# Fermento.net
KiCad netlist of a schematic drawn in EAGLE
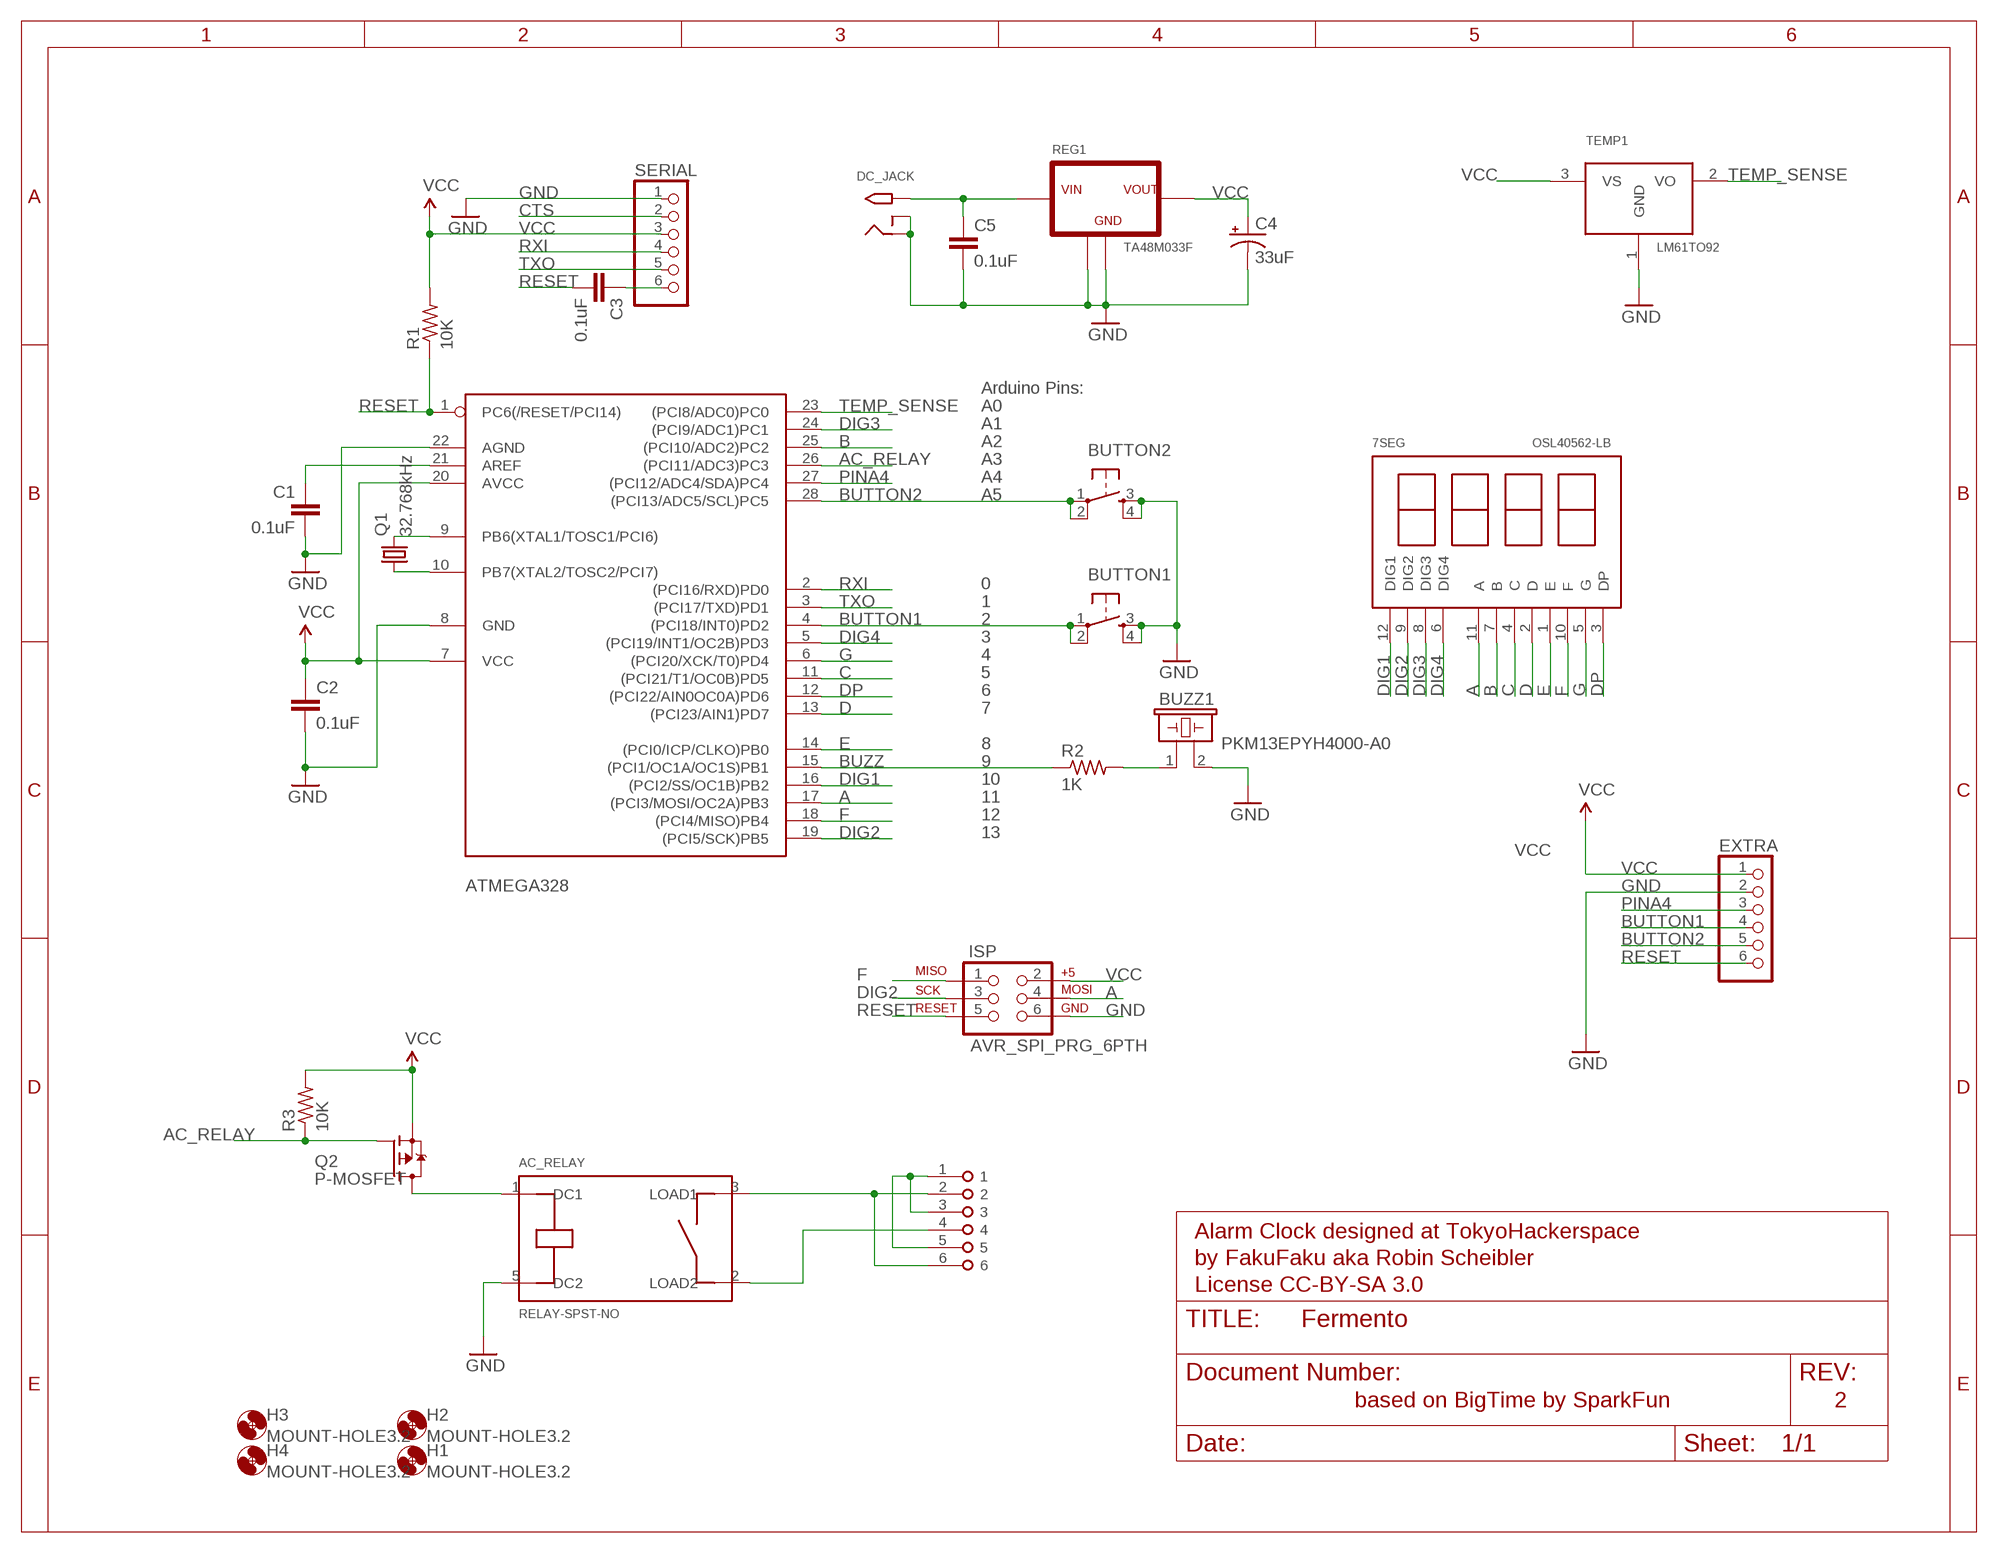
[diagram p0: schematic, sheet 1]

(export (version "E")
  (design (tool "Eeschema 10.0.6"))
  (components
    (comp (ref "7SEG")
      (value "OSL40562-LB")
      (footprint "eagle-import:OSL40562")
      (libsource (lib "eagle-import") (part "7SEG"))
    )
    (comp (ref "AC_RELAY")
      (value "RELAY-SPST-NO")
      (footprint "eagle-import:G6RL-1A-DC3")
      (libsource (lib "eagle-import") (part "RELAY-SPST-NO"))
    )
    (comp (ref "ATMEGA328")
      (value "ATMEGA168-20P")
      (footprint "eagle-import:DIL28-3")
      (libsource (lib "eagle-import") (part "ATMEGA168P-20"))
    )
    (comp (ref "BUTTON1")
      (value "TAC_SWITCHPTH")
      (footprint "eagle-import:TACTILE-PTH")
      (libsource (lib "eagle-import") (part "TAC_SWITCHPTH"))
    )
    (comp (ref "BUTTON2")
      (value "TAC_SWITCHPTH")
      (footprint "eagle-import:TACTILE-PTH")
      (libsource (lib "eagle-import") (part "TAC_SWITCHPTH"))
    )
    (comp (ref "BUZZ1")
      (value "PKM13EPYH4000-A0")
      (footprint "eagle-import:PIEZO-MURATA-13MM")
      (libsource (lib "eagle-import") (part "BUZZER13MM"))
    )
    (comp (ref "C1")
      (value "0.1uF")
      (footprint "eagle-import:CAP-PTH-SMALL")
      (libsource (lib "eagle-import") (part "CAPPTH"))
    )
    (comp (ref "C2")
      (value "0.1uF")
      (footprint "eagle-import:CAP-PTH-SMALL")
      (libsource (lib "eagle-import") (part "CAPPTH"))
    )
    (comp (ref "C3")
      (value "0.1uF")
      (footprint "eagle-import:CAP-PTH-SMALL")
      (libsource (lib "eagle-import") (part "CAPPTH"))
    )
    (comp (ref "C4")
      (value "33uF")
      (footprint "eagle-import:CPOL-RADIAL-10UF-25V")
      (libsource (lib "eagle-import") (part "CAP_POLPTH2"))
    )
    (comp (ref "C5")
      (value "0.1uF")
      (footprint "eagle-import:CAP-PTH-SMALL")
      (libsource (lib "eagle-import") (part "CAPPTH"))
    )
    (comp (ref "DC_JACK")
      (value "2.1MMJACKTHM")
      (footprint "eagle-import:PJ-102A")
      (libsource (lib "eagle-import") (part "2.1MMJACKTHM"))
    )
    (comp (ref "EXTRA")
      (value "PINHD-1X6")
      (footprint "eagle-import:1X06")
      (libsource (lib "eagle-import") (part "PINHD-1X6"))
    )
    (comp (ref "H1")
      (value "MOUNT-HOLE3.2")
      (footprint "eagle-import:3,2")
      (libsource (lib "eagle-import") (part "MOUNT-HOLE3.2"))
    )
    (comp (ref "H2")
      (value "MOUNT-HOLE3.2")
      (footprint "eagle-import:3,2")
      (libsource (lib "eagle-import") (part "MOUNT-HOLE3.2"))
    )
    (comp (ref "H3")
      (value "MOUNT-HOLE3.2")
      (footprint "eagle-import:3,2")
      (libsource (lib "eagle-import") (part "MOUNT-HOLE3.2"))
    )
    (comp (ref "H4")
      (value "MOUNT-HOLE3.2")
      (footprint "eagle-import:3,2")
      (libsource (lib "eagle-import") (part "MOUNT-HOLE3.2"))
    )
    (comp (ref "ISP")
      (value "AVR_SPI_PRG_6PTH")
      (footprint "eagle-import:2X3")
      (libsource (lib "eagle-import") (part "AVR_SPI_PRG_6PTH"))
    )
    (comp (ref "Q1")
      (value "32.768kHz")
      (footprint "eagle-import:CRYSTAL-8X3-TH")
      (libsource (lib "eagle-import") (part "CRYSTAL8X3"))
    )
    (comp (ref "Q2")
      (value "P-MOSFET")
      (footprint "eagle-import:TO92-")
      (libsource (lib "eagle-import") (part "P-MOSFET"))
    )
    (comp (ref "R1")
      (value "10K")
      (footprint "eagle-import:0207_10")
      (libsource (lib "eagle-import") (part "R-US_0207/10"))
    )
    (comp (ref "R2")
      (value "1K")
      (footprint "eagle-import:0207_10")
      (libsource (lib "eagle-import") (part "R-US_0207/10"))
    )
    (comp (ref "R3")
      (value "10K")
      (footprint "eagle-import:0207_10")
      (libsource (lib "eagle-import") (part "R-US_0207/10"))
    )
    (comp (ref "REG1")
      (value "TA48M033F")
      (footprint "eagle-import:TO-220")
      (libsource (lib "eagle-import") (part "REGULATOR-TO-220"))
    )
    (comp (ref "SERIAL")
      (value "PINHD-1X6/90")
      (footprint "eagle-import:1X06_90")
      (libsource (lib "eagle-import") (part "PINHD-1X6/90"))
    )
    (comp (ref "TEMP1")
      (value "LM61TO92")
      (footprint "eagle-import:TO92-")
      (libsource (lib "eagle-import") (part "LM61TO92"))
    )
    (comp (ref "U$2")
      (value "TERMINAL-6")
      (footprint "eagle-import:MBE-156")
      (libsource (lib "eagle-import") (part "TERMINAL-6"))
    )
  )
  (nets
    (net (code "1") (name "/A") (class "Default")
      (node (ref "7SEG") (pin "11") (pinfunction "A_11") (pintype "bidirectional"))
      (node (ref "ATMEGA328") (pin "17") (pinfunction "(PCI3/MOSI/OC2A)PB3_17") (pintype "bidirectional"))
      (node (ref "ISP") (pin "4") (pinfunction "4_4") (pintype "passive"))
    )
    (net (code "2") (name "/AC_RELAY") (class "Default")
      (node (ref "ATMEGA328") (pin "26") (pinfunction "(PCI11/ADC3)PC3_26") (pintype "bidirectional"))
      (node (ref "Q2") (pin "2") (pinfunction "G_2") (pintype "passive"))
      (node (ref "R3") (pin "1") (pinfunction "1_1") (pintype "passive"))
    )
    (net (code "3") (name "/B") (class "Default")
      (node (ref "7SEG") (pin "7") (pinfunction "B_7") (pintype "bidirectional"))
      (node (ref "ATMEGA328") (pin "25") (pinfunction "(PCI10/ADC2)PC2_25") (pintype "bidirectional"))
    )
    (net (code "4") (name "/BUTTON1") (class "Default")
      (node (ref "ATMEGA328") (pin "4") (pinfunction "(PCI18/INT0)PD2_4") (pintype "bidirectional"))
      (node (ref "BUTTON1") (pin "1") (pinfunction "1_1") (pintype "passive"))
      (node (ref "BUTTON1") (pin "2") (pinfunction "2_2") (pintype "passive"))
      (node (ref "EXTRA") (pin "4") (pinfunction "4_4") (pintype "passive"))
    )
    (net (code "5") (name "/BUTTON2") (class "Default")
      (node (ref "ATMEGA328") (pin "28") (pinfunction "(PCI13/ADC5/SCL)PC5_28") (pintype "bidirectional"))
      (node (ref "BUTTON2") (pin "1") (pinfunction "1_1") (pintype "passive"))
      (node (ref "BUTTON2") (pin "2") (pinfunction "2_2") (pintype "passive"))
      (node (ref "EXTRA") (pin "5") (pinfunction "5_5") (pintype "passive"))
    )
    (net (code "6") (name "/BUZZ") (class "Default")
      (node (ref "ATMEGA328") (pin "15") (pinfunction "(PCI1/OC1A/OC1S)PB1_15") (pintype "bidirectional"))
      (node (ref "R2") (pin "1") (pinfunction "1_1") (pintype "passive"))
    )
    (net (code "7") (name "/C") (class "Default")
      (node (ref "7SEG") (pin "4") (pinfunction "C_4") (pintype "bidirectional"))
      (node (ref "ATMEGA328") (pin "11") (pinfunction "(PCI21/T1/OC0B)PD5_11") (pintype "bidirectional"))
    )
    (net (code "8") (name "/CTS") (class "Default")
      (node (ref "SERIAL") (pin "2") (pinfunction "2_2") (pintype "passive"))
    )
    (net (code "9") (name "/D") (class "Default")
      (node (ref "7SEG") (pin "2") (pinfunction "D_2") (pintype "bidirectional"))
      (node (ref "ATMEGA328") (pin "13") (pinfunction "(PCI23/AIN1)PD7_13") (pintype "bidirectional"))
    )
    (net (code "10") (name "/DIG1") (class "Default")
      (node (ref "7SEG") (pin "12") (pinfunction "DIG1_12") (pintype "bidirectional"))
      (node (ref "ATMEGA328") (pin "16") (pinfunction "(PCI2/SS/OC1B)PB2_16") (pintype "bidirectional"))
    )
    (net (code "11") (name "/DIG2") (class "Default")
      (node (ref "7SEG") (pin "9") (pinfunction "DIG2_9") (pintype "bidirectional"))
      (node (ref "ATMEGA328") (pin "19") (pinfunction "(PCI5/SCK)PB5_19") (pintype "bidirectional"))
      (node (ref "ISP") (pin "3") (pinfunction "3_3") (pintype "passive"))
    )
    (net (code "12") (name "/DIG3") (class "Default")
      (node (ref "7SEG") (pin "8") (pinfunction "DIG3_8") (pintype "bidirectional"))
      (node (ref "ATMEGA328") (pin "24") (pinfunction "(PCI9/ADC1)PC1_24") (pintype "bidirectional"))
    )
    (net (code "13") (name "/DIG4") (class "Default")
      (node (ref "7SEG") (pin "6") (pinfunction "DIG4_6") (pintype "bidirectional"))
      (node (ref "ATMEGA328") (pin "5") (pinfunction "(PCI19/INT1/OC2B)PD3_5") (pintype "bidirectional"))
    )
    (net (code "14") (name "/DP") (class "Default")
      (node (ref "7SEG") (pin "3") (pinfunction "DP_3") (pintype "bidirectional"))
      (node (ref "ATMEGA328") (pin "12") (pinfunction "(PCI22/AIN0OC0A)PD6_12") (pintype "bidirectional"))
    )
    (net (code "15") (name "/E") (class "Default")
      (node (ref "7SEG") (pin "1") (pinfunction "E_1") (pintype "bidirectional"))
      (node (ref "ATMEGA328") (pin "14") (pinfunction "(PCI0/ICP/CLKO)PB0_14") (pintype "bidirectional"))
    )
    (net (code "16") (name "/F") (class "Default")
      (node (ref "7SEG") (pin "10") (pinfunction "F_10") (pintype "bidirectional"))
      (node (ref "ATMEGA328") (pin "18") (pinfunction "(PCI4/MISO)PB4_18") (pintype "bidirectional"))
      (node (ref "ISP") (pin "1") (pinfunction "1_1") (pintype "passive"))
    )
    (net (code "17") (name "/G") (class "Default")
      (node (ref "7SEG") (pin "5") (pinfunction "G_5") (pintype "bidirectional"))
      (node (ref "ATMEGA328") (pin "6") (pinfunction "(PCI20/XCK/T0)PD4_6") (pintype "bidirectional"))
    )
    (net (code "18") (name "/PINA4") (class "Default")
      (node (ref "ATMEGA328") (pin "27") (pinfunction "(PCI12/ADC4/SDA)PC4_27") (pintype "bidirectional"))
      (node (ref "EXTRA") (pin "3") (pinfunction "3_3") (pintype "passive"))
    )
    (net (code "19") (name "/RESET") (class "Default")
      (node (ref "ATMEGA328") (pin "1") (pinfunction "PC6(/RESET/PCI14)_1") (pintype "bidirectional"))
      (node (ref "C3") (pin "2") (pinfunction "2_2") (pintype "passive"))
      (node (ref "EXTRA") (pin "6") (pinfunction "6_6") (pintype "passive"))
      (node (ref "ISP") (pin "5") (pinfunction "5_5") (pintype "passive"))
      (node (ref "R1") (pin "1") (pinfunction "1_1") (pintype "passive"))
    )
    (net (code "20") (name "/RXI") (class "Default")
      (node (ref "ATMEGA328") (pin "2") (pinfunction "(PCI16/RXD)PD0_2") (pintype "bidirectional"))
      (node (ref "SERIAL") (pin "4") (pinfunction "4_4") (pintype "passive"))
    )
    (net (code "21") (name "/TEMP_SENSE") (class "Default")
      (node (ref "ATMEGA328") (pin "23") (pinfunction "(PCI8/ADC0)PC0_23") (pintype "bidirectional"))
      (node (ref "TEMP1") (pin "2") (pinfunction "VO_2") (pintype "bidirectional"))
    )
    (net (code "22") (name "/TXO") (class "Default")
      (node (ref "ATMEGA328") (pin "3") (pinfunction "(PCI17/TXD)PD1_3") (pintype "bidirectional"))
      (node (ref "SERIAL") (pin "5") (pinfunction "5_5") (pintype "passive"))
    )
    (net (code "23") (name "GND") (class "Default")
      (node (ref "AC_RELAY") (pin "5") (pinfunction "DC2_5") (pintype "bidirectional"))
      (node (ref "ATMEGA328") (pin "22") (pinfunction "AGND_22") (pintype "bidirectional"))
      (node (ref "ATMEGA328") (pin "8") (pinfunction "GND_8") (pintype "bidirectional"))
      (node (ref "BUTTON1") (pin "3") (pinfunction "3_3") (pintype "passive"))
      (node (ref "BUTTON1") (pin "4") (pinfunction "4_4") (pintype "passive"))
      (node (ref "BUTTON2") (pin "3") (pinfunction "3_3") (pintype "passive"))
      (node (ref "BUTTON2") (pin "4") (pinfunction "4_4") (pintype "passive"))
      (node (ref "BUZZ1") (pin "2") (pinfunction "2_2") (pintype "passive"))
      (node (ref "C1") (pin "2") (pinfunction "2_2") (pintype "passive"))
      (node (ref "C2") (pin "2") (pinfunction "2_2") (pintype "passive"))
      (node (ref "C4") (pin "2") (pinfunction "-_2") (pintype "passive"))
      (node (ref "C5") (pin "2") (pinfunction "2_2") (pintype "passive"))
      (node (ref "DC_JACK") (pin "RING") (pinfunction "RING_RING") (pintype "bidirectional"))
      (node (ref "DC_JACK") (pin "RING_SW") (pinfunction "RING_SW_RING_SW") (pintype "bidirectional"))
      (node (ref "EXTRA") (pin "2") (pinfunction "2_2") (pintype "passive"))
      (node (ref "ISP") (pin "6") (pinfunction "6_6") (pintype "passive"))
      (node (ref "REG1") (pin "CENTER") (pinfunction "GND_CENTER") (pintype "power_in"))
      (node (ref "REG1") (pin "THERMAL") (pinfunction "GND_THERMAL") (pintype "power_in"))
      (node (ref "SERIAL") (pin "1") (pinfunction "1_1") (pintype "passive"))
      (node (ref "TEMP1") (pin "1") (pinfunction "GND_1") (pintype "bidirectional"))
    )
    (net (code "24") (name "Net-(AC_RELAY-DC1)") (class "Default")
      (node (ref "AC_RELAY") (pin "1") (pinfunction "DC1_1") (pintype "bidirectional"))
      (node (ref "Q2") (pin "1") (pinfunction "D_1") (pintype "passive"))
    )
    (net (code "25") (name "Net-(AC_RELAY-LOAD1)") (class "Default")
      (node (ref "AC_RELAY") (pin "3") (pinfunction "LOAD1_3") (pintype "bidirectional"))
      (node (ref "U$2") (pin "2") (pinfunction "2_2") (pintype "bidirectional"))
      (node (ref "U$2") (pin "6") (pinfunction "6_6") (pintype "bidirectional"))
    )
    (net (code "26") (name "Net-(AC_RELAY-LOAD2)") (class "Default")
      (node (ref "AC_RELAY") (pin "2") (pinfunction "LOAD2_2") (pintype "bidirectional"))
      (node (ref "U$2") (pin "4") (pinfunction "4_4") (pintype "bidirectional"))
    )
    (net (code "27") (name "Net-(ATMEGA328-AREF)") (class "Default")
      (node (ref "ATMEGA328") (pin "21") (pinfunction "AREF_21") (pintype "bidirectional"))
      (node (ref "C1") (pin "1") (pinfunction "1_1") (pintype "passive"))
    )
    (net (code "28") (name "Net-(ATMEGA328-PB6(XTAL1{slash}TOSC1{slash}PCI6))") (class "Default")
      (node (ref "ATMEGA328") (pin "9") (pinfunction "PB6(XTAL1/TOSC1/PCI6)_9") (pintype "bidirectional"))
      (node (ref "Q1") (pin "2") (pinfunction "2_2") (pintype "passive"))
    )
    (net (code "29") (name "Net-(ATMEGA328-PB7(XTAL2{slash}TOSC2{slash}PCI7))") (class "Default")
      (node (ref "ATMEGA328") (pin "10") (pinfunction "PB7(XTAL2/TOSC2/PCI7)_10") (pintype "bidirectional"))
      (node (ref "Q1") (pin "1") (pinfunction "1_1") (pintype "passive"))
    )
    (net (code "30") (name "Net-(BUZZ1-Pad1)") (class "Default")
      (node (ref "BUZZ1") (pin "1") (pinfunction "1_1") (pintype "passive"))
      (node (ref "R2") (pin "2") (pinfunction "2_2") (pintype "passive"))
    )
    (net (code "31") (name "Net-(C3-Pad1)") (class "Default")
      (node (ref "C3") (pin "1") (pinfunction "1_1") (pintype "passive"))
      (node (ref "SERIAL") (pin "6") (pinfunction "6_6") (pintype "passive"))
    )
    (net (code "32") (name "Net-(REG1-VIN)") (class "Default")
      (node (ref "C5") (pin "1") (pinfunction "1_1") (pintype "passive"))
      (node (ref "DC_JACK") (pin "TIP") (pinfunction "TIP_TIP") (pintype "bidirectional"))
      (node (ref "REG1") (pin "LEFT") (pinfunction "VIN_LEFT") (pintype "input"))
    )
    (net (code "33") (name "Net-(U$2-Pad1)") (class "Default")
      (node (ref "U$2") (pin "1") (pinfunction "1_1") (pintype "bidirectional"))
      (node (ref "U$2") (pin "3") (pinfunction "3_3") (pintype "bidirectional"))
      (node (ref "U$2") (pin "5") (pinfunction "5_5") (pintype "bidirectional"))
    )
    (net (code "34") (name "VCC") (class "Default")
      (node (ref "ATMEGA328") (pin "20") (pinfunction "AVCC_20") (pintype "bidirectional"))
      (node (ref "ATMEGA328") (pin "7") (pinfunction "VCC_7") (pintype "bidirectional"))
      (node (ref "C2") (pin "1") (pinfunction "1_1") (pintype "passive"))
      (node (ref "C4") (pin "1") (pinfunction "+_1") (pintype "passive"))
      (node (ref "EXTRA") (pin "1") (pinfunction "1_1") (pintype "passive"))
      (node (ref "ISP") (pin "2") (pinfunction "2_2") (pintype "passive"))
      (node (ref "Q2") (pin "3") (pinfunction "S_3") (pintype "passive"))
      (node (ref "R1") (pin "2") (pinfunction "2_2") (pintype "passive"))
      (node (ref "R3") (pin "2") (pinfunction "2_2") (pintype "passive"))
      (node (ref "REG1") (pin "RIGHT") (pinfunction "VOUT_RIGHT") (pintype "power_in"))
      (node (ref "SERIAL") (pin "3") (pinfunction "3_3") (pintype "passive"))
      (node (ref "TEMP1") (pin "3") (pinfunction "VS_3") (pintype "bidirectional"))
    )
  )
)
